# MEMS_Microphone_Module.net
KiCad netlist of a schematic drawn in Altium Designer
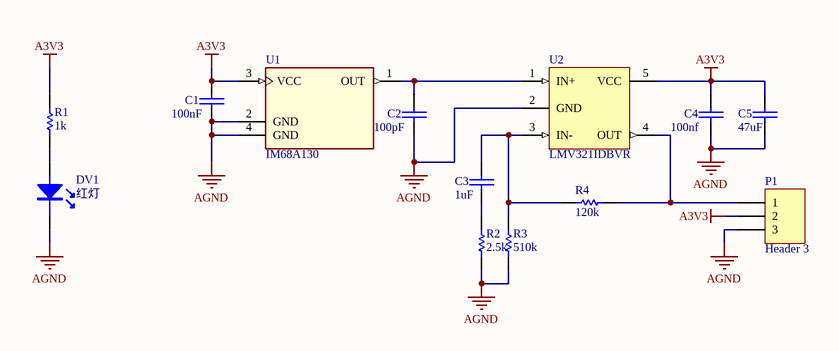
[diagram p0: MEMS Microphone Module.SchDoc]

(export (version "E")
  (design (tool "Eeschema 10.0.6"))
  (components
    (comp (ref "C1")
      (value "100nF")
      (footprint "0603C")
      (description "无极性电容")
      (libsource (lib "电容") (part "CAP"))
    )
    (comp (ref "C2")
      (value "100pF")
      (footprint "0603C")
      (description "无极性电容")
      (libsource (lib "电容") (part "CAP"))
    )
    (comp (ref "C3")
      (value "1uF")
      (footprint "0603C")
      (description "无极性电容")
      (libsource (lib "电容") (part "CAP"))
    )
    (comp (ref "C4")
      (value "100nf")
      (footprint "0603C")
      (description "无极性电容")
      (libsource (lib "电容") (part "CAP"))
    )
    (comp (ref "C5")
      (value "47uF")
      (footprint "0603C")
      (description "无极性电容")
      (libsource (lib "电容") (part "CAP"))
    )
    (comp (ref "DV1") (value "红灯") (footprint "LQ_LED0603R") (libsource (lib "LQ68A130V1") (part "LQ_LED")))
    (comp (ref "P1")
      (value "Header 3")
      (footprint "HDR1X3")
      (description "Header, 3-Pin")
      (fields (field (name "PUBLISHER") "Altium Limited"))
      (libsource (lib "Miscellaneous Connectors") (part "Header 3"))
    )
    (comp (ref "R1") (value "1k") (footprint "0603R") (libsource (lib "电阻") (part "RES")))
    (comp (ref "R2") (value "2.5k") (footprint "0603R") (libsource (lib "电阻") (part "RES")))
    (comp (ref "R3") (value "510k") (footprint "0603R") (libsource (lib "电阻") (part "RES")))
    (comp (ref "R4") (value "120k") (footprint "0603R") (libsource (lib "电阻") (part "RES")))
    (comp (ref "U1")
      (value "IM68A130")
      (footprint "IM68A130")
      (description "High Performance Digital XENSIV MEMS Microphone")
      (fields
        (field (name "MANUFACTURERPARTNUMBER") "IM69D130")
        (field (name "MANUFACTURER") "Infineon Technologies")
      )
      (libsource (lib "LQ68A130V1") (part "IM68A130"))
    )
    (comp (ref "U2")
      (value "LMV321IDBVR")
      (footprint "LQ_SOT-23-5")
      (description "LMV321ID")
      (libsource (lib "LQ68A130V1") (part "LMV321IDBVR"))
    )
  )
  (nets
    (net (code "1") (name "A3V3") (class "Default")
      (node (ref "C1") (pin "2") (pinfunction "2_2") (pintype "passive"))
      (node (ref "C4") (pin "2") (pinfunction "2_2") (pintype "passive"))
      (node (ref "C5") (pin "2") (pinfunction "2_2") (pintype "passive"))
      (node (ref "P1") (pin "2") (pinfunction "2_2") (pintype "passive"))
      (node (ref "R1") (pin "2") (pinfunction "2_2") (pintype "passive"))
      (node (ref "U1") (pin "3") (pinfunction "VCC_3") (pintype "input"))
      (node (ref "U2") (pin "5") (pinfunction "VCC_5") (pintype "power_in"))
    )
    (net (code "2") (name "AGND") (class "Default")
      (node (ref "C1") (pin "1") (pinfunction "1_1") (pintype "passive"))
      (node (ref "C2") (pin "1") (pinfunction "1_1") (pintype "passive"))
      (node (ref "C4") (pin "1") (pinfunction "1_1") (pintype "passive"))
      (node (ref "C5") (pin "1") (pinfunction "1_1") (pintype "passive"))
      (node (ref "DV1") (pin "2") (pinfunction "2_2") (pintype "passive"))
      (node (ref "P1") (pin "3") (pinfunction "3_3") (pintype "passive"))
      (node (ref "R2") (pin "1") (pinfunction "1_1") (pintype "passive"))
      (node (ref "R3") (pin "1") (pinfunction "1_1") (pintype "passive"))
      (node (ref "U1") (pin "2") (pinfunction "GND_2") (pintype "power_in"))
      (node (ref "U1") (pin "4") (pinfunction "GND_4") (pintype "passive"))
      (node (ref "U2") (pin "2") (pinfunction "GND_2") (pintype "power_in"))
    )
    (net (code "3") (name "Net-(C3-Pad1)") (class "Default")
      (node (ref "C3") (pin "1") (pinfunction "1_1") (pintype "passive"))
      (node (ref "R2") (pin "2") (pinfunction "2_2") (pintype "passive"))
    )
    (net (code "4") (name "Net-(DV1-Pad1)") (class "Default")
      (node (ref "DV1") (pin "1") (pinfunction "1_1") (pintype "passive"))
      (node (ref "R1") (pin "1") (pinfunction "1_1") (pintype "passive"))
    )
    (net (code "5") (name "Net-(U1-OUT)") (class "Default")
      (node (ref "C2") (pin "2") (pinfunction "2_2") (pintype "passive"))
      (node (ref "U1") (pin "1") (pinfunction "OUT_1") (pintype "output"))
      (node (ref "U2") (pin "1") (pinfunction "IN+_1") (pintype "input"))
    )
    (net (code "6") (name "Net-(U2-IN-)") (class "Default")
      (node (ref "C3") (pin "2") (pinfunction "2_2") (pintype "passive"))
      (node (ref "R3") (pin "2") (pinfunction "2_2") (pintype "passive"))
      (node (ref "R4") (pin "1") (pinfunction "1_1") (pintype "passive"))
      (node (ref "U2") (pin "3") (pinfunction "IN-_3") (pintype "input"))
    )
    (net (code "7") (name "Net-(U2-OUT)") (class "Default")
      (node (ref "P1") (pin "1") (pinfunction "1_1") (pintype "passive"))
      (node (ref "R4") (pin "2") (pinfunction "2_2") (pintype "passive"))
      (node (ref "U2") (pin "4") (pinfunction "OUT_4") (pintype "output"))
    )
  )
)
